# 01-FPGA_Sources.net
KiCad netlist of a schematic drawn in Altium Designer
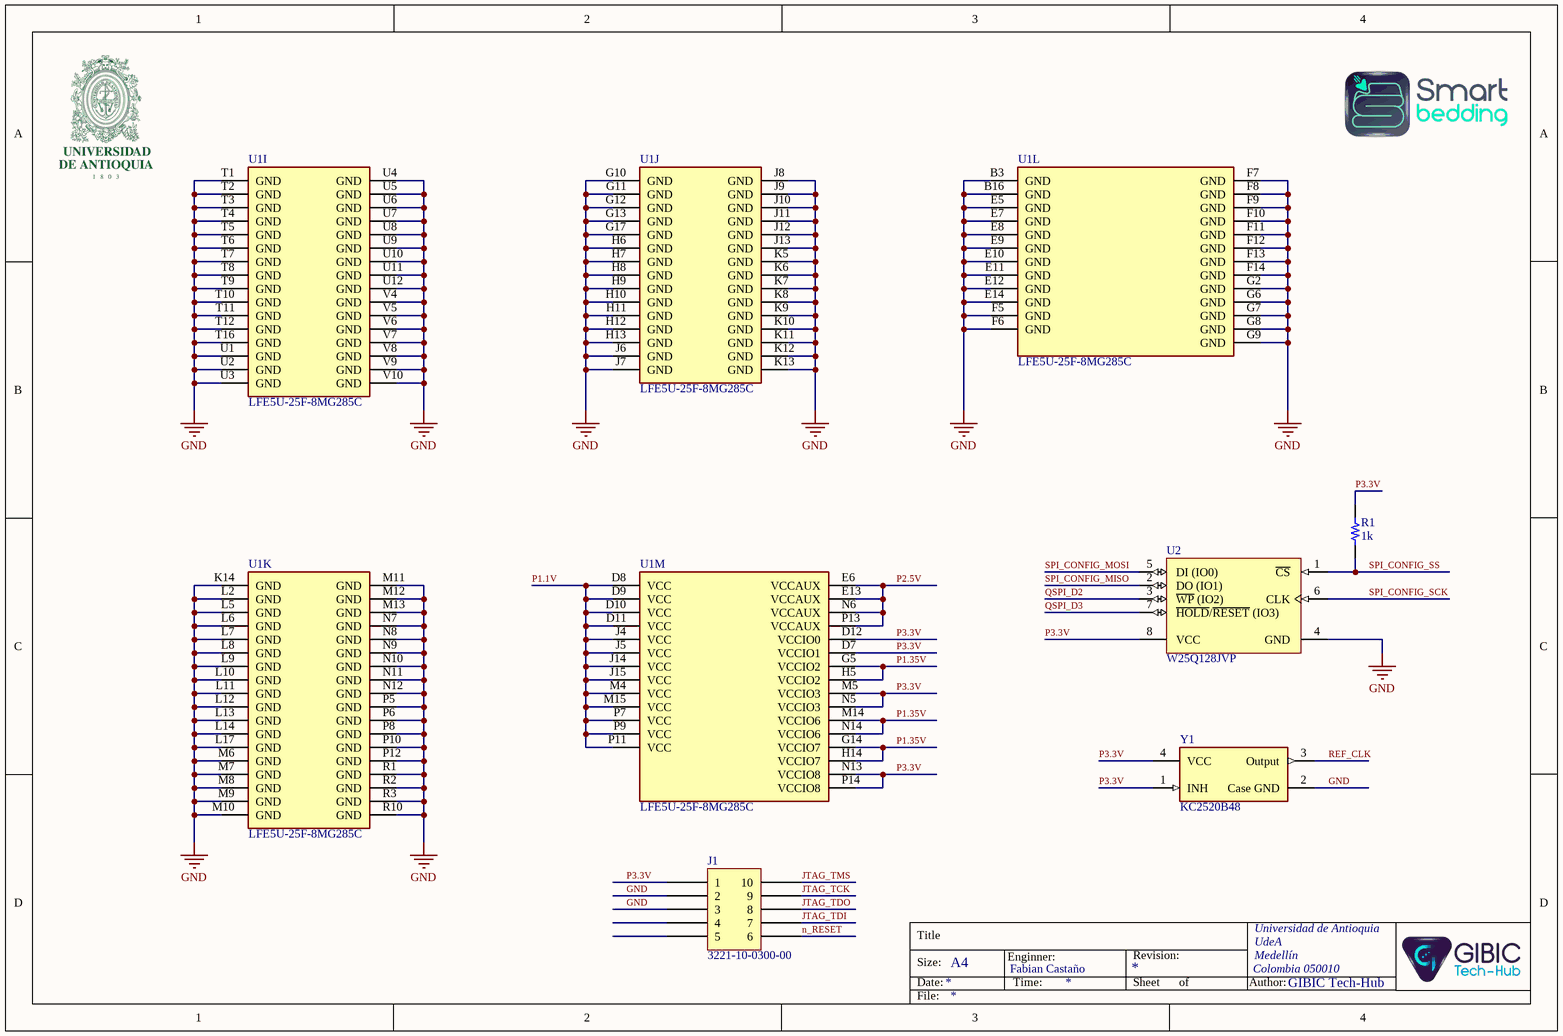
[diagram p0: 01-FPGA_Sources.SchDoc]

(export (version "E")
  (design (tool "Eeschema 10.0.6"))
  (components
    (comp (ref "J1")
      (value "3221-10-0300-00")
      (footprint "CNC TECH 3221-10-0300-00")
      (description "CONN HEADER SMD 10POS 1.27MM")
      (fields
        (field (name "MANUFACTURER") "CNC Tech")
        (field (name "LASTUPDATED") "13/01/2020 12:09:21 a. m.")
      )
      (libsource (lib "Celestial Altium Library - altium_library") (part "2x5 Pin"))
    )
    (comp (ref "R1")
      (value "1k")
      (footprint "RES 0201_0603")
      (description "RES SMD 10K OHM 0.1% 1/20W 0201")
      (fields
        (field (name "PART NUMBER") "ERA-1AEB103C")
        (field (name "MANUFACTURER") "Panasonic Electronic Components")
        (field (name "LASTUPDATED") "3/01/2023 8:15:23 p. m.")
      )
      (libsource (lib "Celestial Altium Library - altium_library") (part "Resistor"))
    )
    (comp (ref "U1")
      (value "LFE5U-25F-8MG285C")
      (footprint "FP-cBGA-LFE5U")
      (description "FPGA LatticeECP5 Family 24000 Cells 40nm Technology 1.1V 285-Pin CSFBGA")
      (libsource (lib "LFE5U-25F-8MG285C") (part "LFE5U-25F-8MG285C"))
    )
    (comp (ref "U2")
      (value "W25Q128JVP")
      (footprint "SON127P500X600X80-9N")
      (description "FLASH - NOR Memory IC 128Mb (16M x 8) SPI - Quad I/O, QPI, DTR 133 MHz 8-WSON (6x5)")
      (libsource (lib "W25Q128JVP") (part "W25Q128JVP"))
    )
    (comp (ref "Y1")
      (value "KC2520B48")
      (footprint "FP-KC2520B-MFG")
      (libsource (lib "KC2520B48") (part "KC2520B48"))
    )
  )
  (nets
    (net (code "1") (name "/JTAG_TCK") (class "Default")
      (node (ref "J1") (pin "9") (pinfunction "9_9") (pintype "passive"))
    )
    (net (code "2") (name "/JTAG_TDI") (class "Default")
      (node (ref "J1") (pin "7") (pinfunction "7_7") (pintype "passive"))
    )
    (net (code "3") (name "/JTAG_TDO") (class "Default")
      (node (ref "J1") (pin "8") (pinfunction "8_8") (pintype "passive"))
    )
    (net (code "4") (name "/JTAG_TMS") (class "Default")
      (node (ref "J1") (pin "10") (pinfunction "10_10") (pintype "passive"))
    )
    (net (code "5") (name "/P1.1V") (class "Default")
      (node (ref "U1") (pin "D10") (pinfunction "VCC_D10") (pintype "power_in"))
      (node (ref "U1") (pin "D11") (pinfunction "VCC_D11") (pintype "power_in"))
      (node (ref "U1") (pin "D8") (pinfunction "VCC_D8") (pintype "power_in"))
      (node (ref "U1") (pin "D9") (pinfunction "VCC_D9") (pintype "power_in"))
      (node (ref "U1") (pin "J14") (pinfunction "VCC_J14") (pintype "power_in"))
      (node (ref "U1") (pin "J15") (pinfunction "VCC_J15") (pintype "power_in"))
      (node (ref "U1") (pin "J4") (pinfunction "VCC_J4") (pintype "power_in"))
      (node (ref "U1") (pin "J5") (pinfunction "VCC_J5") (pintype "power_in"))
      (node (ref "U1") (pin "M15") (pinfunction "VCC_M15") (pintype "power_in"))
      (node (ref "U1") (pin "M4") (pinfunction "VCC_M4") (pintype "power_in"))
      (node (ref "U1") (pin "P11") (pinfunction "VCC_P11") (pintype "power_in"))
      (node (ref "U1") (pin "P7") (pinfunction "VCC_P7") (pintype "power_in"))
      (node (ref "U1") (pin "P9") (pinfunction "VCC_P9") (pintype "power_in"))
    )
    (net (code "6") (name "/P1.35V") (class "Default")
      (node (ref "U1") (pin "G14") (pinfunction "VCCIO7_G14") (pintype "power_in"))
      (node (ref "U1") (pin "G5") (pinfunction "VCCIO2_G5") (pintype "power_in"))
      (node (ref "U1") (pin "H14") (pinfunction "VCCIO7_H14") (pintype "power_in"))
      (node (ref "U1") (pin "H5") (pinfunction "VCCIO2_H5") (pintype "power_in"))
      (node (ref "U1") (pin "M14") (pinfunction "VCCIO6_M14") (pintype "power_in"))
      (node (ref "U1") (pin "N14") (pinfunction "VCCIO6_N14") (pintype "power_in"))
    )
    (net (code "7") (name "/P2.5V") (class "Default")
      (node (ref "U1") (pin "E13") (pinfunction "VCCAUX_E13") (pintype "power_in"))
      (node (ref "U1") (pin "E6") (pinfunction "VCCAUX_E6") (pintype "power_in"))
      (node (ref "U1") (pin "N6") (pinfunction "VCCAUX_N6") (pintype "power_in"))
      (node (ref "U1") (pin "P13") (pinfunction "VCCAUX_P13") (pintype "power_in"))
    )
    (net (code "8") (name "/P3.3V") (class "Default")
      (node (ref "J1") (pin "1") (pinfunction "1_1") (pintype "passive"))
      (node (ref "R1") (pin "1") (pinfunction "1_1") (pintype "passive"))
      (node (ref "U1") (pin "D12") (pinfunction "VCCIO0_D12") (pintype "power_in"))
      (node (ref "U1") (pin "D7") (pinfunction "VCCIO1_D7") (pintype "power_in"))
      (node (ref "U1") (pin "M5") (pinfunction "VCCIO3_M5") (pintype "power_in"))
      (node (ref "U1") (pin "N13") (pinfunction "VCCIO8_N13") (pintype "power_in"))
      (node (ref "U1") (pin "N5") (pinfunction "VCCIO3_N5") (pintype "power_in"))
      (node (ref "U1") (pin "P14") (pinfunction "VCCIO8_P14") (pintype "power_in"))
      (node (ref "U2") (pin "8") (pinfunction "VCC_8") (pintype "power_in"))
      (node (ref "Y1") (pin "1") (pinfunction "INH_1") (pintype "input"))
      (node (ref "Y1") (pin "4") (pinfunction "VCC_4") (pintype "power_in"))
    )
    (net (code "9") (name "/QSPI_D2") (class "Default")
      (node (ref "U2") (pin "3") (pinfunction "~{WP}_(IO2)_3") (pintype "bidirectional"))
    )
    (net (code "10") (name "/QSPI_D3") (class "Default")
      (node (ref "U2") (pin "7") (pinfunction "~{HOLD}/~{RESET}_(IO3)_7") (pintype "bidirectional"))
    )
    (net (code "11") (name "/REF_CLK") (class "Default")
      (node (ref "Y1") (pin "3") (pinfunction "Output_3") (pintype "output"))
    )
    (net (code "12") (name "/SPI_CONFIG_MISO") (class "Default")
      (node (ref "U2") (pin "2") (pinfunction "DO_(IO1)_2") (pintype "bidirectional"))
    )
    (net (code "13") (name "/SPI_CONFIG_MOSI") (class "Default")
      (node (ref "U2") (pin "5") (pinfunction "DI_(IO0)_5") (pintype "bidirectional"))
    )
    (net (code "14") (name "/SPI_CONFIG_SCK") (class "Default")
      (node (ref "U2") (pin "6") (pinfunction "CLK_6") (pintype "input"))
    )
    (net (code "15") (name "/SPI_CONFIG_SS") (class "Default")
      (node (ref "R1") (pin "2") (pinfunction "2_2") (pintype "passive"))
      (node (ref "U2") (pin "1") (pinfunction "~{CS}_1") (pintype "input"))
    )
    (net (code "16") (name "/n_RESET") (class "Default")
      (node (ref "J1") (pin "6") (pinfunction "6_6") (pintype "passive"))
    )
    (net (code "17") (name "GND") (class "Default")
      (node (ref "J1") (pin "2") (pinfunction "2_2") (pintype "passive"))
      (node (ref "J1") (pin "3") (pinfunction "3_3") (pintype "passive"))
      (node (ref "U1") (pin "B16") (pinfunction "GND_B16") (pintype "power_in"))
      (node (ref "U1") (pin "B3") (pinfunction "GND_B3") (pintype "power_in"))
      (node (ref "U1") (pin "E10") (pinfunction "GND_E10") (pintype "power_in"))
      (node (ref "U1") (pin "E11") (pinfunction "GND_E11") (pintype "power_in"))
      (node (ref "U1") (pin "E12") (pinfunction "GND_E12") (pintype "power_in"))
      (node (ref "U1") (pin "E14") (pinfunction "GND_E14") (pintype "power_in"))
      (node (ref "U1") (pin "E5") (pinfunction "GND_E5") (pintype "power_in"))
      (node (ref "U1") (pin "E7") (pinfunction "GND_E7") (pintype "power_in"))
      (node (ref "U1") (pin "E8") (pinfunction "GND_E8") (pintype "power_in"))
      (node (ref "U1") (pin "E9") (pinfunction "GND_E9") (pintype "power_in"))
      (node (ref "U1") (pin "F10") (pinfunction "GND_F10") (pintype "power_in"))
      (node (ref "U1") (pin "F11") (pinfunction "GND_F11") (pintype "power_in"))
      (node (ref "U1") (pin "F12") (pinfunction "GND_F12") (pintype "power_in"))
      (node (ref "U1") (pin "F13") (pinfunction "GND_F13") (pintype "power_in"))
      (node (ref "U1") (pin "F14") (pinfunction "GND_F14") (pintype "power_in"))
      (node (ref "U1") (pin "F5") (pinfunction "GND_F5") (pintype "power_in"))
      (node (ref "U1") (pin "F6") (pinfunction "GND_F6") (pintype "power_in"))
      (node (ref "U1") (pin "F7") (pinfunction "GND_F7") (pintype "power_in"))
      (node (ref "U1") (pin "F8") (pinfunction "GND_F8") (pintype "power_in"))
      (node (ref "U1") (pin "F9") (pinfunction "GND_F9") (pintype "power_in"))
      (node (ref "U1") (pin "G10") (pinfunction "GND_G10") (pintype "power_in"))
      (node (ref "U1") (pin "G11") (pinfunction "GND_G11") (pintype "power_in"))
      (node (ref "U1") (pin "G12") (pinfunction "GND_G12") (pintype "power_in"))
      (node (ref "U1") (pin "G13") (pinfunction "GND_G13") (pintype "power_in"))
      (node (ref "U1") (pin "G17") (pinfunction "GND_G17") (pintype "power_in"))
      (node (ref "U1") (pin "G2") (pinfunction "GND_G2") (pintype "power_in"))
      (node (ref "U1") (pin "G6") (pinfunction "GND_G6") (pintype "power_in"))
      (node (ref "U1") (pin "G7") (pinfunction "GND_G7") (pintype "power_in"))
      (node (ref "U1") (pin "G8") (pinfunction "GND_G8") (pintype "power_in"))
      (node (ref "U1") (pin "G9") (pinfunction "GND_G9") (pintype "power_in"))
      (node (ref "U1") (pin "H10") (pinfunction "GND_H10") (pintype "power_in"))
      (node (ref "U1") (pin "H11") (pinfunction "GND_H11") (pintype "power_in"))
      (node (ref "U1") (pin "H12") (pinfunction "GND_H12") (pintype "power_in"))
      (node (ref "U1") (pin "H13") (pinfunction "GND_H13") (pintype "power_in"))
      (node (ref "U1") (pin "H6") (pinfunction "GND_H6") (pintype "power_in"))
      (node (ref "U1") (pin "H7") (pinfunction "GND_H7") (pintype "power_in"))
      (node (ref "U1") (pin "H8") (pinfunction "GND_H8") (pintype "power_in"))
      (node (ref "U1") (pin "H9") (pinfunction "GND_H9") (pintype "power_in"))
      (node (ref "U1") (pin "J10") (pinfunction "GND_J10") (pintype "power_in"))
      (node (ref "U1") (pin "J11") (pinfunction "GND_J11") (pintype "power_in"))
      (node (ref "U1") (pin "J12") (pinfunction "GND_J12") (pintype "power_in"))
      (node (ref "U1") (pin "J13") (pinfunction "GND_J13") (pintype "power_in"))
      (node (ref "U1") (pin "J6") (pinfunction "GND_J6") (pintype "power_in"))
      (node (ref "U1") (pin "J7") (pinfunction "GND_J7") (pintype "power_in"))
      (node (ref "U1") (pin "J8") (pinfunction "GND_J8") (pintype "power_in"))
      (node (ref "U1") (pin "J9") (pinfunction "GND_J9") (pintype "power_in"))
      (node (ref "U1") (pin "K10") (pinfunction "GND_K10") (pintype "power_in"))
      (node (ref "U1") (pin "K11") (pinfunction "GND_K11") (pintype "power_in"))
      (node (ref "U1") (pin "K12") (pinfunction "GND_K12") (pintype "power_in"))
      (node (ref "U1") (pin "K13") (pinfunction "GND_K13") (pintype "power_in"))
      (node (ref "U1") (pin "K14") (pinfunction "GND_K14") (pintype "power_in"))
      (node (ref "U1") (pin "K5") (pinfunction "GND_K5") (pintype "power_in"))
      (node (ref "U1") (pin "K6") (pinfunction "GND_K6") (pintype "power_in"))
      (node (ref "U1") (pin "K7") (pinfunction "GND_K7") (pintype "power_in"))
      (node (ref "U1") (pin "K8") (pinfunction "GND_K8") (pintype "power_in"))
      (node (ref "U1") (pin "K9") (pinfunction "GND_K9") (pintype "power_in"))
      (node (ref "U1") (pin "L10") (pinfunction "GND_L10") (pintype "power_in"))
      (node (ref "U1") (pin "L11") (pinfunction "GND_L11") (pintype "power_in"))
      (node (ref "U1") (pin "L12") (pinfunction "GND_L12") (pintype "power_in"))
      (node (ref "U1") (pin "L13") (pinfunction "GND_L13") (pintype "power_in"))
      (node (ref "U1") (pin "L14") (pinfunction "GND_L14") (pintype "power_in"))
      (node (ref "U1") (pin "L17") (pinfunction "GND_L17") (pintype "power_in"))
      (node (ref "U1") (pin "L2") (pinfunction "GND_L2") (pintype "power_in"))
      (node (ref "U1") (pin "L5") (pinfunction "GND_L5") (pintype "power_in"))
      (node (ref "U1") (pin "L6") (pinfunction "GND_L6") (pintype "power_in"))
      (node (ref "U1") (pin "L7") (pinfunction "GND_L7") (pintype "power_in"))
      (node (ref "U1") (pin "L8") (pinfunction "GND_L8") (pintype "power_in"))
      (node (ref "U1") (pin "L9") (pinfunction "GND_L9") (pintype "power_in"))
      (node (ref "U1") (pin "M10") (pinfunction "GND_M10") (pintype "power_in"))
      (node (ref "U1") (pin "M11") (pinfunction "GND_M11") (pintype "power_in"))
      (node (ref "U1") (pin "M12") (pinfunction "GND_M12") (pintype "power_in"))
      (node (ref "U1") (pin "M13") (pinfunction "GND_M13") (pintype "power_in"))
      (node (ref "U1") (pin "M6") (pinfunction "GND_M6") (pintype "power_in"))
      (node (ref "U1") (pin "M7") (pinfunction "GND_M7") (pintype "power_in"))
      (node (ref "U1") (pin "M8") (pinfunction "GND_M8") (pintype "power_in"))
      (node (ref "U1") (pin "M9") (pinfunction "GND_M9") (pintype "power_in"))
      (node (ref "U1") (pin "N10") (pinfunction "GND_N10") (pintype "power_in"))
      (node (ref "U1") (pin "N11") (pinfunction "GND_N11") (pintype "power_in"))
      (node (ref "U1") (pin "N12") (pinfunction "GND_N12") (pintype "power_in"))
      (node (ref "U1") (pin "N7") (pinfunction "GND_N7") (pintype "power_in"))
      (node (ref "U1") (pin "N8") (pinfunction "GND_N8") (pintype "power_in"))
      (node (ref "U1") (pin "N9") (pinfunction "GND_N9") (pintype "power_in"))
      (node (ref "U1") (pin "P10") (pinfunction "GND_P10") (pintype "power_in"))
      (node (ref "U1") (pin "P12") (pinfunction "GND_P12") (pintype "power_in"))
      (node (ref "U1") (pin "P5") (pinfunction "GND_P5") (pintype "power_in"))
      (node (ref "U1") (pin "P6") (pinfunction "GND_P6") (pintype "power_in"))
      (node (ref "U1") (pin "P8") (pinfunction "GND_P8") (pintype "power_in"))
      (node (ref "U1") (pin "R1") (pinfunction "GND_R1") (pintype "power_in"))
      (node (ref "U1") (pin "R10") (pinfunction "GND_R10") (pintype "power_in"))
      (node (ref "U1") (pin "R2") (pinfunction "GND_R2") (pintype "power_in"))
      (node (ref "U1") (pin "R3") (pinfunction "GND_R3") (pintype "power_in"))
      (node (ref "U1") (pin "T1") (pinfunction "GND_T1") (pintype "power_in"))
      (node (ref "U1") (pin "T10") (pinfunction "GND_T10") (pintype "power_in"))
      (node (ref "U1") (pin "T11") (pinfunction "GND_T11") (pintype "power_in"))
      (node (ref "U1") (pin "T12") (pinfunction "GND_T12") (pintype "power_in"))
      (node (ref "U1") (pin "T16") (pinfunction "GND_T16") (pintype "power_in"))
      (node (ref "U1") (pin "T2") (pinfunction "GND_T2") (pintype "power_in"))
      (node (ref "U1") (pin "T3") (pinfunction "GND_T3") (pintype "power_in"))
      (node (ref "U1") (pin "T4") (pinfunction "GND_T4") (pintype "power_in"))
      (node (ref "U1") (pin "T5") (pinfunction "GND_T5") (pintype "power_in"))
      (node (ref "U1") (pin "T6") (pinfunction "GND_T6") (pintype "power_in"))
      (node (ref "U1") (pin "T7") (pinfunction "GND_T7") (pintype "power_in"))
      (node (ref "U1") (pin "T8") (pinfunction "GND_T8") (pintype "power_in"))
      (node (ref "U1") (pin "T9") (pinfunction "GND_T9") (pintype "power_in"))
      (node (ref "U1") (pin "U1") (pinfunction "GND_U1") (pintype "power_in"))
      (node (ref "U1") (pin "U10") (pinfunction "GND_U10") (pintype "power_in"))
      (node (ref "U1") (pin "U11") (pinfunction "GND_U11") (pintype "power_in"))
      (node (ref "U1") (pin "U12") (pinfunction "GND_U12") (pintype "power_in"))
      (node (ref "U1") (pin "U2") (pinfunction "GND_U2") (pintype "power_in"))
      (node (ref "U1") (pin "U3") (pinfunction "GND_U3") (pintype "power_in"))
      (node (ref "U1") (pin "U4") (pinfunction "GND_U4") (pintype "power_in"))
      (node (ref "U1") (pin "U5") (pinfunction "GND_U5") (pintype "power_in"))
      (node (ref "U1") (pin "U6") (pinfunction "GND_U6") (pintype "power_in"))
      (node (ref "U1") (pin "U7") (pinfunction "GND_U7") (pintype "power_in"))
      (node (ref "U1") (pin "U8") (pinfunction "GND_U8") (pintype "power_in"))
      (node (ref "U1") (pin "U9") (pinfunction "GND_U9") (pintype "power_in"))
      (node (ref "U1") (pin "V10") (pinfunction "GND_V10") (pintype "power_in"))
      (node (ref "U1") (pin "V4") (pinfunction "GND_V4") (pintype "power_in"))
      (node (ref "U1") (pin "V5") (pinfunction "GND_V5") (pintype "power_in"))
      (node (ref "U1") (pin "V6") (pinfunction "GND_V6") (pintype "power_in"))
      (node (ref "U1") (pin "V7") (pinfunction "GND_V7") (pintype "power_in"))
      (node (ref "U1") (pin "V8") (pinfunction "GND_V8") (pintype "power_in"))
      (node (ref "U1") (pin "V9") (pinfunction "GND_V9") (pintype "power_in"))
      (node (ref "U2") (pin "4") (pinfunction "GND_4") (pintype "power_in"))
      (node (ref "Y1") (pin "2") (pinfunction "Case_GND_2") (pintype "power_in"))
    )
    (net (code "18") (name "unconnected-(J1-Pad4)") (class "Default")
      (node (ref "J1") (pin "4") (pinfunction "4_4") (pintype "passive"))
    )
    (net (code "19") (name "unconnected-(J1-Pad5)") (class "Default")
      (node (ref "J1") (pin "5") (pinfunction "5_5") (pintype "passive"))
    )
  )
)
